# pcb1.net
KiCad netlist of a schematic drawn in EAGLE
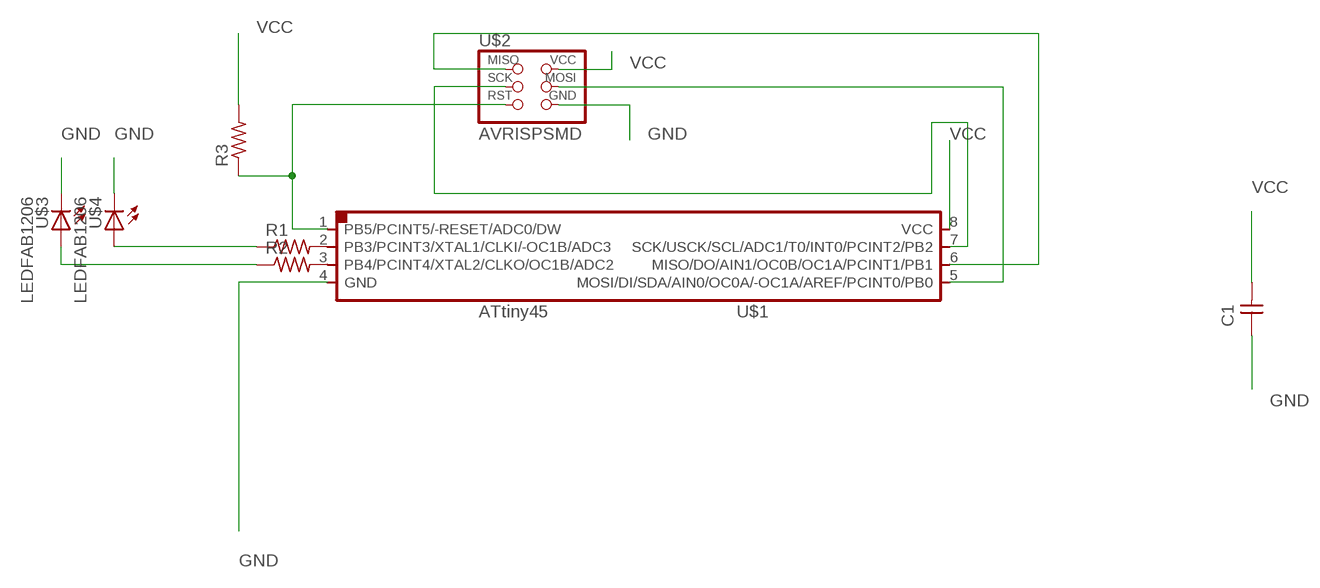
[diagram p0: schematic, sheet 1]

(export (version "E")
  (design (tool "Eeschema 10.0.6"))
  (components
    (comp (ref "C1")
      (value "CAP-UNPOLARIZED")
      (footprint "eagle-import:C1206")
      (libsource (lib "eagle-import") (part "CAP-UNPOLARIZED"))
    )
    (comp (ref "R1")
      (value "RES-US1206FAB")
      (footprint "eagle-import:R1206FAB")
      (libsource (lib "eagle-import") (part "RES-US1206FAB"))
    )
    (comp (ref "R2")
      (value "RES-US1206FAB")
      (footprint "eagle-import:R1206FAB")
      (libsource (lib "eagle-import") (part "RES-US1206FAB"))
    )
    (comp (ref "R3")
      (value "RES-US1206FAB")
      (footprint "eagle-import:R1206FAB")
      (libsource (lib "eagle-import") (part "RES-US1206FAB"))
    )
    (comp (ref "U$1")
      (value "ATTINY45SI")
      (footprint "eagle-import:SOIC8")
      (libsource (lib "eagle-import") (part "ATTINY45SI"))
    )
    (comp (ref "U$2")
      (value "AVRISPSMD")
      (footprint "eagle-import:2X03SMD")
      (libsource (lib "eagle-import") (part "AVRISPSMD"))
    )
    (comp (ref "U$3")
      (value "LEDFAB1206")
      (footprint "eagle-import:LED1206FAB")
      (libsource (lib "eagle-import") (part "LEDFAB1206"))
    )
    (comp (ref "U$4")
      (value "LEDFAB1206")
      (footprint "eagle-import:LED1206FAB")
      (libsource (lib "eagle-import") (part "LEDFAB1206"))
    )
  )
  (nets
    (net (code "1") (name "/GND") (class "Default")
      (node (ref "C1") (pin "1") (pinfunction "1_1") (pintype "passive"))
      (node (ref "U$1") (pin "4") (pinfunction "GND_4") (pintype "bidirectional"))
      (node (ref "U$2") (pin "6") (pinfunction "GND_6") (pintype "passive"))
      (node (ref "U$3") (pin "2") (pinfunction "C_2") (pintype "passive"))
      (node (ref "U$4") (pin "2") (pinfunction "C_2") (pintype "passive"))
    )
    (net (code "2") (name "/VCC") (class "Default")
      (node (ref "C1") (pin "2") (pinfunction "2_2") (pintype "passive"))
      (node (ref "R3") (pin "2") (pinfunction "2_2") (pintype "passive"))
      (node (ref "U$1") (pin "8") (pinfunction "VCC_8") (pintype "bidirectional"))
      (node (ref "U$2") (pin "2") (pinfunction "VCC_2") (pintype "passive"))
    )
    (net (code "3") (name "Net-(U$1-MISO{slash}DO{slash}AIN1{slash}OC0B{slash}OC1A{slash}PCINT1{slash}PB1)") (class "Default")
      (node (ref "U$1") (pin "6") (pinfunction "MISO/DO/AIN1/OC0B/OC1A/PCINT1/PB1_6") (pintype "bidirectional"))
      (node (ref "U$2") (pin "1") (pinfunction "MISO_1") (pintype "passive"))
    )
    (net (code "4") (name "Net-(U$1-MOSI{slash}DI{slash}SDA{slash}AIN0{slash}OC0A{slash}-OC1A{slash}AREF{slash}PCINT0{slash}PB0)") (class "Default")
      (node (ref "U$1") (pin "5") (pinfunction "MOSI/DI/SDA/AIN0/OC0A/-OC1A/AREF/PCINT0/PB0_5") (pintype "bidirectional"))
      (node (ref "U$2") (pin "4") (pinfunction "MOSI_4") (pintype "passive"))
    )
    (net (code "5") (name "Net-(U$1-PB3{slash}PCINT3{slash}XTAL1{slash}CLKI{slash}-OC1B{slash}ADC3)") (class "Default")
      (node (ref "R1") (pin "2") (pinfunction "2_2") (pintype "passive"))
      (node (ref "U$1") (pin "2") (pinfunction "PB3/PCINT3/XTAL1/CLKI/-OC1B/ADC3_2") (pintype "bidirectional"))
    )
    (net (code "6") (name "Net-(U$1-PB4{slash}PCINT4{slash}XTAL2{slash}CLKO{slash}OC1B{slash}ADC2)") (class "Default")
      (node (ref "R2") (pin "2") (pinfunction "2_2") (pintype "passive"))
      (node (ref "U$1") (pin "3") (pinfunction "PB4/PCINT4/XTAL2/CLKO/OC1B/ADC2_3") (pintype "bidirectional"))
    )
    (net (code "7") (name "Net-(U$1-PB5{slash}PCINT5{slash}-RESET{slash}ADC0{slash}DW)") (class "Default")
      (node (ref "R3") (pin "1") (pinfunction "1_1") (pintype "passive"))
      (node (ref "U$1") (pin "1") (pinfunction "PB5/PCINT5/-RESET/ADC0/DW_1") (pintype "bidirectional"))
      (node (ref "U$2") (pin "5") (pinfunction "RST_5") (pintype "passive"))
    )
    (net (code "8") (name "Net-(U$1-SCK{slash}USCK{slash}SCL{slash}ADC1{slash}T0{slash}INT0{slash}PCINT2{slash}PB2)") (class "Default")
      (node (ref "U$1") (pin "7") (pinfunction "SCK/USCK/SCL/ADC1/T0/INT0/PCINT2/PB2_7") (pintype "bidirectional"))
      (node (ref "U$2") (pin "3") (pinfunction "SCK_3") (pintype "passive"))
    )
    (net (code "9") (name "Net-(U$3-A)") (class "Default")
      (node (ref "R2") (pin "1") (pinfunction "1_1") (pintype "passive"))
      (node (ref "U$3") (pin "1") (pinfunction "A_1") (pintype "passive"))
    )
    (net (code "10") (name "Net-(U$4-A)") (class "Default")
      (node (ref "R1") (pin "1") (pinfunction "1_1") (pintype "passive"))
      (node (ref "U$4") (pin "1") (pinfunction "A_1") (pintype "passive"))
    )
  )
)
